# Mosfetboard.net
KiCad netlist of a schematic drawn in EAGLE
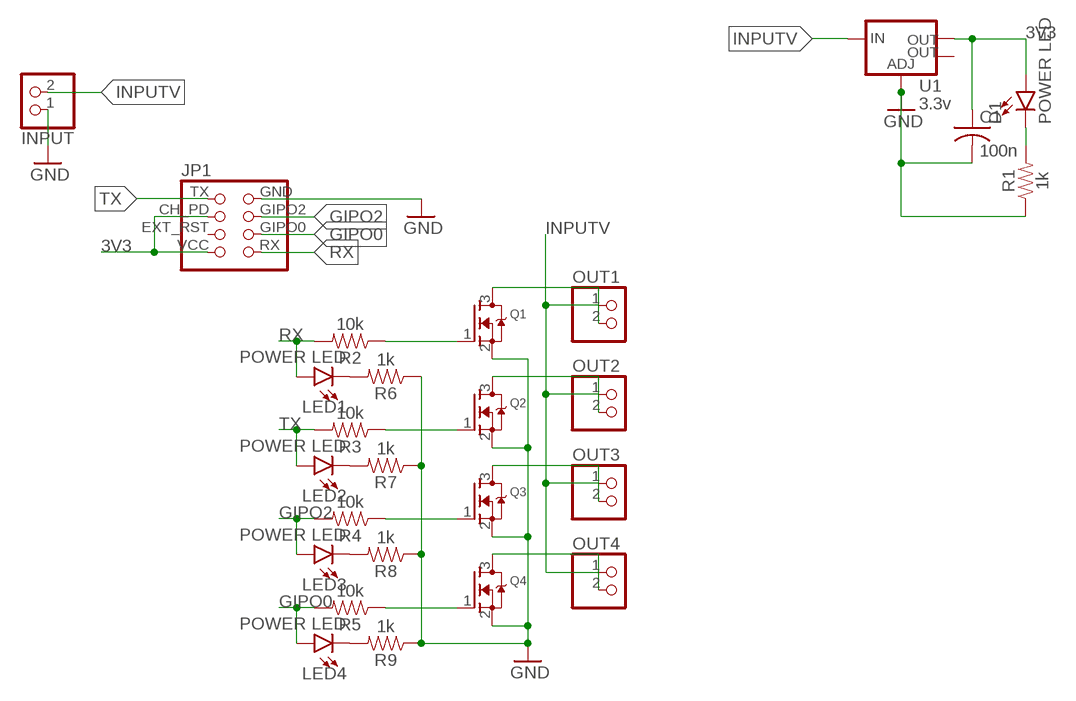
[diagram p0: schematic, sheet 1]

(export (version "E")
  (design (tool "Eeschema 10.0.6"))
  (components
    (comp (ref "C1")
      (value "100n")
      (footprint "eagle-import:C1206K")
      (libsource (lib "eagle-import") (part "C-USC1206K"))
    )
    (comp (ref "D1")
      (value "POWER LED")
      (footprint "eagle-import:LED-0805")
      (libsource (lib "eagle-import") (part "LED-BLUE0805"))
    )
    (comp (ref "INPUT")
      (value "PINHD-1X2")
      (footprint "eagle-import:1X02")
      (libsource (lib "eagle-import") (part "PINHD-1X2"))
    )
    (comp (ref "JP1")
      (value "ESP-01-FEMALE")
      (footprint "eagle-import:ESP-01-FEMALE")
      (libsource (lib "eagle-import") (part "ESP-01-FEMALE"))
    )
    (comp (ref "LED1")
      (value "POWER LED")
      (footprint "eagle-import:LED-0805")
      (libsource (lib "eagle-import") (part "LED-BLUE0805"))
    )
    (comp (ref "LED2")
      (value "POWER LED")
      (footprint "eagle-import:LED-0805")
      (libsource (lib "eagle-import") (part "LED-BLUE0805"))
    )
    (comp (ref "LED3")
      (value "POWER LED")
      (footprint "eagle-import:LED-0805")
      (libsource (lib "eagle-import") (part "LED-BLUE0805"))
    )
    (comp (ref "LED4")
      (value "POWER LED")
      (footprint "eagle-import:LED-0805")
      (libsource (lib "eagle-import") (part "LED-BLUE0805"))
    )
    (comp (ref "OUT1")
      (value "PINHD-1X2")
      (footprint "eagle-import:1X02")
      (libsource (lib "eagle-import") (part "PINHD-1X2"))
    )
    (comp (ref "OUT2")
      (value "PINHD-1X2")
      (footprint "eagle-import:1X02")
      (libsource (lib "eagle-import") (part "PINHD-1X2"))
    )
    (comp (ref "OUT3")
      (value "PINHD-1X2")
      (footprint "eagle-import:1X02")
      (libsource (lib "eagle-import") (part "PINHD-1X2"))
    )
    (comp (ref "OUT4")
      (value "PINHD-1X2")
      (footprint "eagle-import:1X02")
      (libsource (lib "eagle-import") (part "PINHD-1X2"))
    )
    (comp (ref "Q1")
      (value "MOSFET-NREFLOW")
      (footprint "eagle-import:SOT23")
      (libsource (lib "eagle-import") (part "MOSFET-NREFLOW"))
    )
    (comp (ref "Q2")
      (value "MOSFET-NREFLOW")
      (footprint "eagle-import:SOT23")
      (libsource (lib "eagle-import") (part "MOSFET-NREFLOW"))
    )
    (comp (ref "Q3")
      (value "MOSFET-NREFLOW")
      (footprint "eagle-import:SOT23")
      (libsource (lib "eagle-import") (part "MOSFET-NREFLOW"))
    )
    (comp (ref "Q4")
      (value "MOSFET-NREFLOW")
      (footprint "eagle-import:SOT23")
      (libsource (lib "eagle-import") (part "MOSFET-NREFLOW"))
    )
    (comp (ref "R1")
      (value "1k")
      (footprint "eagle-import:0805")
      (libsource (lib "eagle-import") (part "RESISTOR0805"))
    )
    (comp (ref "R2")
      (value "10k")
      (footprint "eagle-import:0805")
      (libsource (lib "eagle-import") (part "RESISTOR0805"))
    )
    (comp (ref "R3")
      (value "10k")
      (footprint "eagle-import:0805")
      (libsource (lib "eagle-import") (part "RESISTOR0805"))
    )
    (comp (ref "R4")
      (value "10k")
      (footprint "eagle-import:0805")
      (libsource (lib "eagle-import") (part "RESISTOR0805"))
    )
    (comp (ref "R5")
      (value "10k")
      (footprint "eagle-import:0805")
      (libsource (lib "eagle-import") (part "RESISTOR0805"))
    )
    (comp (ref "R6")
      (value "1k")
      (footprint "eagle-import:0805")
      (libsource (lib "eagle-import") (part "RESISTOR0805"))
    )
    (comp (ref "R7")
      (value "1k")
      (footprint "eagle-import:0805")
      (libsource (lib "eagle-import") (part "RESISTOR0805"))
    )
    (comp (ref "R8")
      (value "1k")
      (footprint "eagle-import:0805")
      (libsource (lib "eagle-import") (part "RESISTOR0805"))
    )
    (comp (ref "R9")
      (value "1k")
      (footprint "eagle-import:0805")
      (libsource (lib "eagle-import") (part "RESISTOR0805"))
    )
    (comp (ref "U1")
      (value "3.3v")
      (footprint "eagle-import:SOT223")
      (libsource (lib "eagle-import") (part "V_REG_LM1117SOT223"))
    )
  )
  (nets
    (net (code "1") (name "/3V3") (class "Default")
      (node (ref "C1") (pin "1") (pinfunction "1_1") (pintype "passive"))
      (node (ref "D1") (pin "+") (pinfunction "A_+") (pintype "passive"))
      (node (ref "JP1") (pin "CH_PD") (pinfunction "CHIP_EN_CH_PD") (pintype "passive"))
      (node (ref "JP1") (pin "VCC") (pinfunction "VCC_VCC") (pintype "passive"))
      (node (ref "U1") (pin "2") (pinfunction "OUT_2") (pintype "output"))
    )
    (net (code "2") (name "GIPO0") (class "Default")
      (node (ref "JP1") (pin "GIPO0") (pinfunction "GIPO0_GIPO0") (pintype "passive"))
      (node (ref "LED4") (pin "+") (pinfunction "A_+") (pintype "passive"))
      (node (ref "R5") (pin "2") (pinfunction "2_2") (pintype "passive"))
    )
    (net (code "3") (name "GIPO2") (class "Default")
      (node (ref "JP1") (pin "GIPO2") (pinfunction "GIPO2_GIPO2") (pintype "passive"))
      (node (ref "LED3") (pin "+") (pinfunction "A_+") (pintype "passive"))
      (node (ref "R4") (pin "2") (pinfunction "2_2") (pintype "passive"))
    )
    (net (code "4") (name "GND") (class "Default")
      (node (ref "C1") (pin "2") (pinfunction "2_2") (pintype "passive"))
      (node (ref "INPUT") (pin "1") (pinfunction "1_1") (pintype "passive"))
      (node (ref "JP1") (pin "GND") (pinfunction "GND_GND") (pintype "passive"))
      (node (ref "Q1") (pin "2") (pinfunction "S_2") (pintype "bidirectional"))
      (node (ref "Q2") (pin "2") (pinfunction "S_2") (pintype "bidirectional"))
      (node (ref "Q3") (pin "2") (pinfunction "S_2") (pintype "bidirectional"))
      (node (ref "Q4") (pin "2") (pinfunction "S_2") (pintype "bidirectional"))
      (node (ref "R1") (pin "1") (pinfunction "1_1") (pintype "passive"))
      (node (ref "R6") (pin "1") (pinfunction "1_1") (pintype "passive"))
      (node (ref "R7") (pin "1") (pinfunction "1_1") (pintype "passive"))
      (node (ref "R8") (pin "1") (pinfunction "1_1") (pintype "passive"))
      (node (ref "R9") (pin "1") (pinfunction "1_1") (pintype "passive"))
      (node (ref "U1") (pin "1") (pinfunction "ADJ_1") (pintype "input"))
    )
    (net (code "5") (name "INPUTV") (class "Default")
      (node (ref "INPUT") (pin "2") (pinfunction "2_2") (pintype "passive"))
      (node (ref "OUT1") (pin "1") (pinfunction "1_1") (pintype "passive"))
      (node (ref "OUT2") (pin "1") (pinfunction "1_1") (pintype "passive"))
      (node (ref "OUT3") (pin "1") (pinfunction "1_1") (pintype "passive"))
      (node (ref "OUT4") (pin "1") (pinfunction "1_1") (pintype "passive"))
      (node (ref "U1") (pin "3") (pinfunction "IN_3") (pintype "input"))
    )
    (net (code "6") (name "Net-(D1-C)") (class "Default")
      (node (ref "D1") (pin "-") (pinfunction "C_-") (pintype "passive"))
      (node (ref "R1") (pin "2") (pinfunction "2_2") (pintype "passive"))
    )
    (net (code "7") (name "Net-(LED1-C)") (class "Default")
      (node (ref "LED1") (pin "-") (pinfunction "C_-") (pintype "passive"))
      (node (ref "R6") (pin "2") (pinfunction "2_2") (pintype "passive"))
    )
    (net (code "8") (name "Net-(LED2-C)") (class "Default")
      (node (ref "LED2") (pin "-") (pinfunction "C_-") (pintype "passive"))
      (node (ref "R7") (pin "2") (pinfunction "2_2") (pintype "passive"))
    )
    (net (code "9") (name "Net-(LED3-C)") (class "Default")
      (node (ref "LED3") (pin "-") (pinfunction "C_-") (pintype "passive"))
      (node (ref "R8") (pin "2") (pinfunction "2_2") (pintype "passive"))
    )
    (net (code "10") (name "Net-(LED4-C)") (class "Default")
      (node (ref "LED4") (pin "-") (pinfunction "C_-") (pintype "passive"))
      (node (ref "R9") (pin "2") (pinfunction "2_2") (pintype "passive"))
    )
    (net (code "11") (name "Net-(Q1-D)") (class "Default")
      (node (ref "OUT1") (pin "2") (pinfunction "2_2") (pintype "passive"))
      (node (ref "Q1") (pin "3") (pinfunction "D_3") (pintype "bidirectional"))
    )
    (net (code "12") (name "Net-(Q1-G)") (class "Default")
      (node (ref "Q1") (pin "1") (pinfunction "G_1") (pintype "bidirectional"))
      (node (ref "R2") (pin "1") (pinfunction "1_1") (pintype "passive"))
    )
    (net (code "13") (name "Net-(Q2-D)") (class "Default")
      (node (ref "OUT2") (pin "2") (pinfunction "2_2") (pintype "passive"))
      (node (ref "Q2") (pin "3") (pinfunction "D_3") (pintype "bidirectional"))
    )
    (net (code "14") (name "Net-(Q2-G)") (class "Default")
      (node (ref "Q2") (pin "1") (pinfunction "G_1") (pintype "bidirectional"))
      (node (ref "R3") (pin "1") (pinfunction "1_1") (pintype "passive"))
    )
    (net (code "15") (name "Net-(Q3-D)") (class "Default")
      (node (ref "OUT3") (pin "2") (pinfunction "2_2") (pintype "passive"))
      (node (ref "Q3") (pin "3") (pinfunction "D_3") (pintype "bidirectional"))
    )
    (net (code "16") (name "Net-(Q3-G)") (class "Default")
      (node (ref "Q3") (pin "1") (pinfunction "G_1") (pintype "bidirectional"))
      (node (ref "R4") (pin "1") (pinfunction "1_1") (pintype "passive"))
    )
    (net (code "17") (name "Net-(Q4-D)") (class "Default")
      (node (ref "OUT4") (pin "2") (pinfunction "2_2") (pintype "passive"))
      (node (ref "Q4") (pin "3") (pinfunction "D_3") (pintype "bidirectional"))
    )
    (net (code "18") (name "Net-(Q4-G)") (class "Default")
      (node (ref "Q4") (pin "1") (pinfunction "G_1") (pintype "bidirectional"))
      (node (ref "R5") (pin "1") (pinfunction "1_1") (pintype "passive"))
    )
    (net (code "19") (name "RX") (class "Default")
      (node (ref "JP1") (pin "RX") (pinfunction "RX_RX") (pintype "passive"))
      (node (ref "LED1") (pin "+") (pinfunction "A_+") (pintype "passive"))
      (node (ref "R2") (pin "2") (pinfunction "2_2") (pintype "passive"))
    )
    (net (code "20") (name "TX") (class "Default")
      (node (ref "JP1") (pin "TX") (pinfunction "TX_TX") (pintype "passive"))
      (node (ref "LED2") (pin "+") (pinfunction "A_+") (pintype "passive"))
      (node (ref "R3") (pin "2") (pinfunction "2_2") (pintype "passive"))
    )
    (net (code "21") (name "unconnected-(JP1-PadEXT_RST)") (class "Default")
      (node (ref "JP1") (pin "EXT_RST") (pinfunction "EXT_RST_EXT_RST") (pintype "passive"))
    )
    (net (code "22") (name "unconnected-(U1-OUT-Pad4)") (class "Default")
      (node (ref "U1") (pin "4") (pinfunction "OUT_4") (pintype "output"))
    )
  )
)
